# LED_Channel.net
KiCad netlist of a schematic drawn in Altium Designer
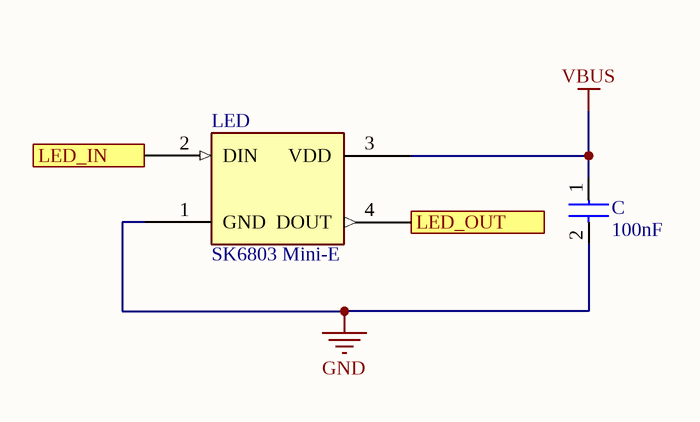
[diagram p0: LED_Channel.SchDoc]

(export (version "E")
  (design (tool "Eeschema 10.0.6"))
  (components
    (comp (ref "C")
      (value "100nF")
      (footprint "CL10B104KA8NNNC")
      (fields (field (name "LCSC PART #") "C1590"))
      (libsource (lib "PCBDEV_Library") (part "CAP NP"))
    )
    (comp (ref "LED")
      (value "SK6803 Mini-E")
      (footprint "SK6803 MINI-E")
      (libsource (lib "KeyBored_PCB_ThomasLajoie_2025") (part "SK6803 Mini-E"))
    )
  )
  (nets
    (net (code "1") (name "/LED_IN") (class "Default")
      (node (ref "LED") (pin "2") (pinfunction "DIN_2") (pintype "input"))
    )
    (net (code "2") (name "/LED_OUT") (class "Default")
      (node (ref "LED") (pin "4") (pinfunction "DOUT_4") (pintype "output"))
    )
    (net (code "3") (name "GND") (class "Default")
      (node (ref "C") (pin "2") (pinfunction "2_2") (pintype "passive"))
      (node (ref "LED") (pin "1") (pinfunction "GND_1") (pintype "power_in"))
    )
    (net (code "4") (name "VBUS") (class "Default")
      (node (ref "C") (pin "1") (pinfunction "1_1") (pintype "passive"))
      (node (ref "LED") (pin "3") (pinfunction "VDD_3") (pintype "power_in"))
    )
  )
)
